# ATTEMP.net
KiCad netlist of a schematic drawn in EAGLE
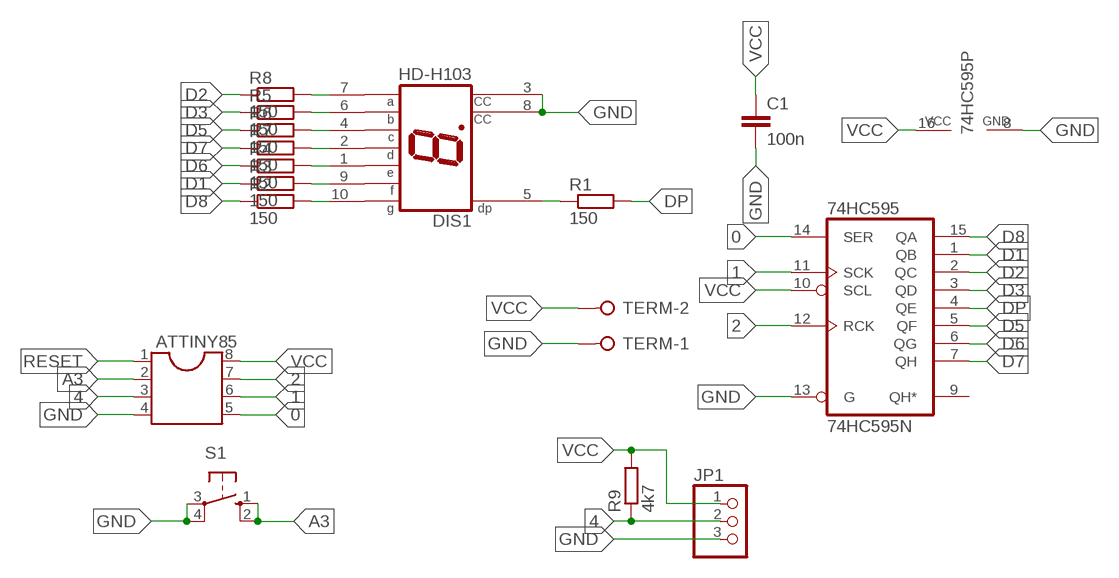
[diagram p0: schematic, sheet 1]

(export (version "E")
  (design (tool "Eeschema 10.0.6"))
  (components
    (comp (ref "74HC595")
      (value "74HC595N")
      (footprint "eagle-import:DIL16")
      (libsource (lib "eagle-import") (part "74595NHC"))
    )
    (comp (ref "ATTINY85")
      (value "DIL8")
      (footprint "eagle-import:DIL08")
      (libsource (lib "eagle-import") (part "DIL8"))
    )
    (comp (ref "C1")
      (value "100n")
      (footprint "eagle-import:C1206")
      (libsource (lib "eagle-import") (part "C-EUC1206"))
    )
    (comp (ref "DIS1")
      (value "HD-H103")
      (footprint "eagle-import:HDSP-M")
      (libsource (lib "eagle-import") (part "HD-H103"))
    )
    (comp (ref "JP1")
      (value "PINHD-1X3")
      (footprint "eagle-import:1X03")
      (libsource (lib "eagle-import") (part "PINHD-1X3"))
    )
    (comp (ref "R1")
      (value "150")
      (footprint "eagle-import:R1206")
      (libsource (lib "eagle-import") (part "R-EU_R1206"))
    )
    (comp (ref "R2")
      (value "150")
      (footprint "eagle-import:R1206")
      (libsource (lib "eagle-import") (part "R-EU_R1206"))
    )
    (comp (ref "R3")
      (value "150")
      (footprint "eagle-import:R1206")
      (libsource (lib "eagle-import") (part "R-EU_R1206"))
    )
    (comp (ref "R4")
      (value "150")
      (footprint "eagle-import:R1206")
      (libsource (lib "eagle-import") (part "R-EU_R1206"))
    )
    (comp (ref "R5")
      (value "150")
      (footprint "eagle-import:R1206")
      (libsource (lib "eagle-import") (part "R-EU_R1206"))
    )
    (comp (ref "R6")
      (value "150")
      (footprint "eagle-import:R1206")
      (libsource (lib "eagle-import") (part "R-EU_R1206"))
    )
    (comp (ref "R7")
      (value "150")
      (footprint "eagle-import:R1206")
      (libsource (lib "eagle-import") (part "R-EU_R1206"))
    )
    (comp (ref "R8")
      (value "150")
      (footprint "eagle-import:R1206")
      (libsource (lib "eagle-import") (part "R-EU_R1206"))
    )
    (comp (ref "R9")
      (value "4k7")
      (footprint "eagle-import:R1206")
      (libsource (lib "eagle-import") (part "R-EU_R1206"))
    )
    (comp (ref "S1")
      (value "10-XX")
      (footprint "eagle-import:B3F-10XX")
      (fields (field (name "MPN") "B3F-1000"))
      (libsource (lib "eagle-import") (part "10-XX"))
    )
    (comp (ref "TERM")
      (value "W237-02P")
      (footprint "eagle-import:W237-132")
      (libsource (lib "eagle-import") (part "W237-02P"))
    )
  )
  (nets
    (net (code "1") (name "0") (class "Default")
      (node (ref "74HC595") (pin "14") (pinfunction "SER_14") (pintype "input"))
      (node (ref "ATTINY85") (pin "5") (pinfunction "5_5") (pintype "passive"))
    )
    (net (code "2") (name "1") (class "Default")
      (node (ref "74HC595") (pin "11") (pinfunction "SCK_11") (pintype "input"))
      (node (ref "ATTINY85") (pin "6") (pinfunction "6_6") (pintype "passive"))
    )
    (net (code "3") (name "2") (class "Default")
      (node (ref "74HC595") (pin "12") (pinfunction "RCK_12") (pintype "input"))
      (node (ref "ATTINY85") (pin "7") (pinfunction "7_7") (pintype "passive"))
    )
    (net (code "4") (name "4") (class "Default")
      (node (ref "ATTINY85") (pin "3") (pinfunction "3_3") (pintype "passive"))
      (node (ref "JP1") (pin "2") (pinfunction "2_2") (pintype "passive"))
      (node (ref "R9") (pin "1") (pinfunction "1_1") (pintype "passive"))
    )
    (net (code "5") (name "A3") (class "Default")
      (node (ref "ATTINY85") (pin "2") (pinfunction "2_2") (pintype "passive"))
      (node (ref "S1") (pin "1") (pinfunction "S_1") (pintype "passive"))
      (node (ref "S1") (pin "2") (pinfunction "S1_2") (pintype "passive"))
    )
    (net (code "6") (name "D1") (class "Default")
      (node (ref "74HC595") (pin "1") (pinfunction "QB_1") (pintype "tri_state"))
      (node (ref "R3") (pin "1") (pinfunction "1_1") (pintype "passive"))
    )
    (net (code "7") (name "D2") (class "Default")
      (node (ref "74HC595") (pin "2") (pinfunction "QC_2") (pintype "tri_state"))
      (node (ref "R8") (pin "1") (pinfunction "1_1") (pintype "passive"))
    )
    (net (code "8") (name "D3") (class "Default")
      (node (ref "74HC595") (pin "3") (pinfunction "QD_3") (pintype "tri_state"))
      (node (ref "R5") (pin "1") (pinfunction "1_1") (pintype "passive"))
    )
    (net (code "9") (name "D5") (class "Default")
      (node (ref "74HC595") (pin "5") (pinfunction "QF_5") (pintype "tri_state"))
      (node (ref "R6") (pin "1") (pinfunction "1_1") (pintype "passive"))
    )
    (net (code "10") (name "D6") (class "Default")
      (node (ref "74HC595") (pin "6") (pinfunction "QG_6") (pintype "tri_state"))
      (node (ref "R4") (pin "1") (pinfunction "1_1") (pintype "passive"))
    )
    (net (code "11") (name "D7") (class "Default")
      (node (ref "74HC595") (pin "7") (pinfunction "QH_7") (pintype "tri_state"))
      (node (ref "R7") (pin "1") (pinfunction "1_1") (pintype "passive"))
    )
    (net (code "12") (name "D8") (class "Default")
      (node (ref "74HC595") (pin "15") (pinfunction "QA_15") (pintype "tri_state"))
      (node (ref "R2") (pin "1") (pinfunction "1_1") (pintype "passive"))
    )
    (net (code "13") (name "DP") (class "Default")
      (node (ref "74HC595") (pin "4") (pinfunction "QE_4") (pintype "tri_state"))
      (node (ref "R1") (pin "2") (pinfunction "2_2") (pintype "passive"))
    )
    (net (code "14") (name "GND") (class "Default")
      (node (ref "74HC595") (pin "13") (pinfunction "G_13") (pintype "input"))
      (node (ref "74HC595") (pin "8") (pinfunction "GND_8") (pintype "power_in"))
      (node (ref "ATTINY85") (pin "4") (pinfunction "4_4") (pintype "passive"))
      (node (ref "C1") (pin "2") (pinfunction "2_2") (pintype "passive"))
      (node (ref "DIS1") (pin "3") (pinfunction "CC_3") (pintype "passive"))
      (node (ref "DIS1") (pin "8") (pinfunction "CC_8") (pintype "passive"))
      (node (ref "JP1") (pin "3") (pinfunction "3_3") (pintype "passive"))
      (node (ref "S1") (pin "3") (pinfunction "P_3") (pintype "passive"))
      (node (ref "S1") (pin "4") (pinfunction "P1_4") (pintype "passive"))
      (node (ref "TERM") (pin "1") (pinfunction "KL_1") (pintype "passive"))
    )
    (net (code "15") (name "Net-(DIS1-A)") (class "Default")
      (node (ref "DIS1") (pin "7") (pinfunction "A_7") (pintype "passive"))
      (node (ref "R8") (pin "2") (pinfunction "2_2") (pintype "passive"))
    )
    (net (code "16") (name "Net-(DIS1-B)") (class "Default")
      (node (ref "DIS1") (pin "6") (pinfunction "B_6") (pintype "passive"))
      (node (ref "R5") (pin "2") (pinfunction "2_2") (pintype "passive"))
    )
    (net (code "17") (name "Net-(DIS1-C)") (class "Default")
      (node (ref "DIS1") (pin "4") (pinfunction "C_4") (pintype "passive"))
      (node (ref "R6") (pin "2") (pinfunction "2_2") (pintype "passive"))
    )
    (net (code "18") (name "Net-(DIS1-D)") (class "Default")
      (node (ref "DIS1") (pin "2") (pinfunction "D_2") (pintype "passive"))
      (node (ref "R7") (pin "2") (pinfunction "2_2") (pintype "passive"))
    )
    (net (code "19") (name "Net-(DIS1-DP)") (class "Default")
      (node (ref "DIS1") (pin "5") (pinfunction "DP_5") (pintype "passive"))
      (node (ref "R1") (pin "1") (pinfunction "1_1") (pintype "passive"))
    )
    (net (code "20") (name "Net-(DIS1-E)") (class "Default")
      (node (ref "DIS1") (pin "1") (pinfunction "E_1") (pintype "passive"))
      (node (ref "R4") (pin "2") (pinfunction "2_2") (pintype "passive"))
    )
    (net (code "21") (name "Net-(DIS1-F)") (class "Default")
      (node (ref "DIS1") (pin "9") (pinfunction "F_9") (pintype "passive"))
      (node (ref "R3") (pin "2") (pinfunction "2_2") (pintype "passive"))
    )
    (net (code "22") (name "Net-(DIS1-G)") (class "Default")
      (node (ref "DIS1") (pin "10") (pinfunction "G_10") (pintype "passive"))
      (node (ref "R2") (pin "2") (pinfunction "2_2") (pintype "passive"))
    )
    (net (code "23") (name "RESET") (class "Default")
      (node (ref "ATTINY85") (pin "1") (pinfunction "1_1") (pintype "passive"))
    )
    (net (code "24") (name "VCC") (class "Default")
      (node (ref "74HC595") (pin "10") (pinfunction "SCL_10") (pintype "input"))
      (node (ref "74HC595") (pin "16") (pinfunction "VCC_16") (pintype "power_in"))
      (node (ref "ATTINY85") (pin "8") (pinfunction "8_8") (pintype "passive"))
      (node (ref "C1") (pin "1") (pinfunction "1_1") (pintype "passive"))
      (node (ref "JP1") (pin "1") (pinfunction "1_1") (pintype "passive"))
      (node (ref "R9") (pin "2") (pinfunction "2_2") (pintype "passive"))
      (node (ref "TERM") (pin "2") (pinfunction "KL_2") (pintype "passive"))
    )
    (net (code "25") (name "unconnected-(74HC595A-QH*-Pad9)") (class "Default")
      (node (ref "74HC595") (pin "9") (pinfunction "QH*_9") (pintype "tri_state"))
    )
  )
)
